# DorMouse-V0_5.net
KiCad netlist of a schematic drawn in EAGLE
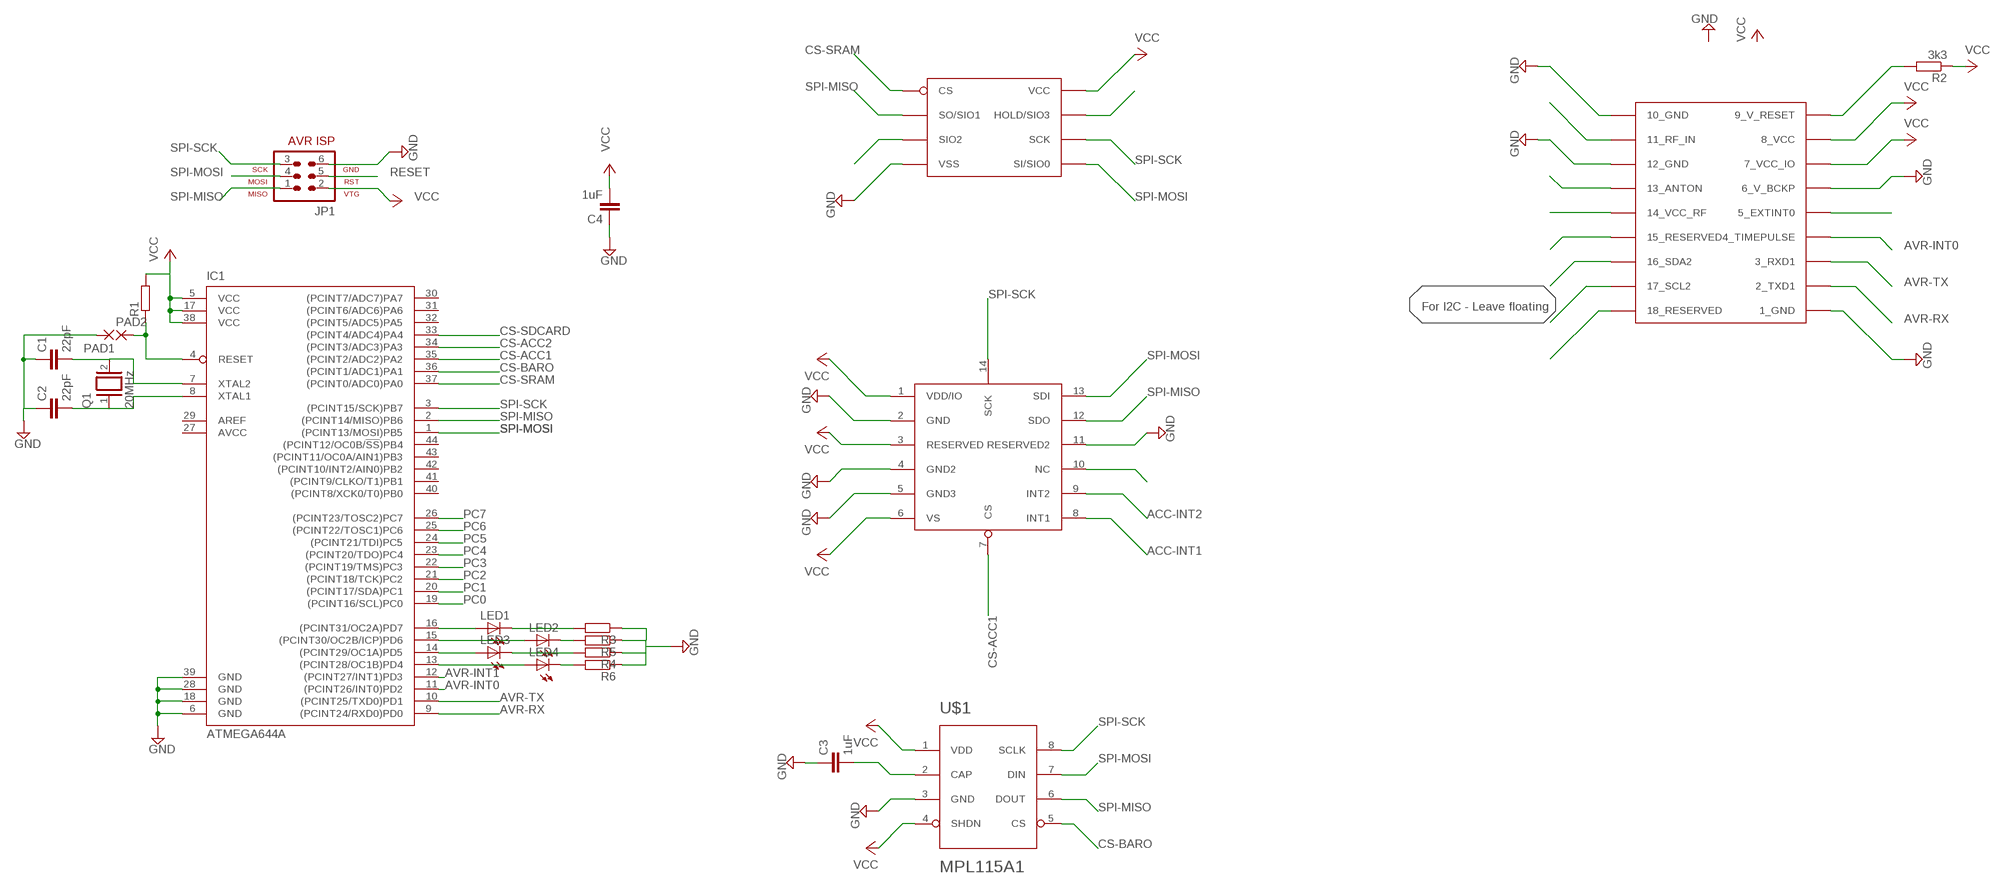
[diagram p0: schematic, sheet 1]

(export (version "E")
  (design (tool "Eeschema 10.0.6"))
  (components
    (comp (ref "C1")
      (value "22pF")
      (footprint "eagle-import:C0402")
      (libsource (lib "eagle-import") (part "C-EUC0402"))
    )
    (comp (ref "C2")
      (value "22pF")
      (footprint "eagle-import:C0402")
      (libsource (lib "eagle-import") (part "C-EUC0402"))
    )
    (comp (ref "C3")
      (value "1uF")
      (footprint "eagle-import:C0402")
      (libsource (lib "eagle-import") (part "C-EUC0402"))
    )
    (comp (ref "C4")
      (value "1uF")
      (footprint "eagle-import:C0402")
      (libsource (lib "eagle-import") (part "C-EUC0402"))
    )
    (comp (ref "IC1")
      (value "ATMEGA644A")
      (footprint "eagle-import:TQFP44")
      (fields (field (name "MPN") "ATMEGA644PV-10AU"))
      (libsource (lib "eagle-import") (part "ATMEGA644A"))
    )
    (comp (ref "JP1")
      (value "AVR-ISP-6")
      (footprint "eagle-import:AVR-ISP-6")
      (libsource (lib "eagle-import") (part "AVR-ISP-6"))
    )
    (comp (ref "LED1")
      (value "LEDCHIP-LED0603")
      (footprint "eagle-import:CHIP-LED0603")
      (libsource (lib "eagle-import") (part "LEDCHIP-LED0603"))
    )
    (comp (ref "LED2")
      (value "LEDCHIP-LED0603")
      (footprint "eagle-import:CHIP-LED0603")
      (libsource (lib "eagle-import") (part "LEDCHIP-LED0603"))
    )
    (comp (ref "LED3")
      (value "LEDCHIP-LED0603")
      (footprint "eagle-import:CHIP-LED0603")
      (libsource (lib "eagle-import") (part "LEDCHIP-LED0603"))
    )
    (comp (ref "LED4")
      (value "LEDCHIP-LED0603")
      (footprint "eagle-import:CHIP-LED0603")
      (libsource (lib "eagle-import") (part "LEDCHIP-LED0603"))
    )
    (comp (ref "PAD1")
      (value "SMD2")
      (footprint "eagle-import:SMD1,27-2,54")
      (libsource (lib "eagle-import") (part "SMD2"))
    )
    (comp (ref "PAD2")
      (value "SMD2")
      (footprint "eagle-import:SMD1,27-2,54")
      (libsource (lib "eagle-import") (part "SMD2"))
    )
    (comp (ref "Q1")
      (value "20MHz")
      (footprint "eagle-import:QS")
      (libsource (lib "eagle-import") (part "XTAL/S"))
    )
    (comp (ref "R1")
      (value "R-EU_R0402")
      (footprint "eagle-import:R0402")
      (libsource (lib "eagle-import") (part "R-EU_R0402"))
    )
    (comp (ref "R2")
      (value "3k3")
      (footprint "eagle-import:R0402")
      (libsource (lib "eagle-import") (part "R-EU_R0402"))
    )
    (comp (ref "R3")
      (value "R-EU_R0402")
      (footprint "eagle-import:R0402")
      (libsource (lib "eagle-import") (part "R-EU_R0402"))
    )
    (comp (ref "R4")
      (value "R-EU_R0402")
      (footprint "eagle-import:R0402")
      (libsource (lib "eagle-import") (part "R-EU_R0402"))
    )
    (comp (ref "R5")
      (value "R-EU_R0402")
      (footprint "eagle-import:R0402")
      (libsource (lib "eagle-import") (part "R-EU_R0402"))
    )
    (comp (ref "R6")
      (value "R-EU_R0402")
      (footprint "eagle-import:R0402")
      (libsource (lib "eagle-import") (part "R-EU_R0402"))
    )
    (comp (ref "SPI-SRAM")
      (value "23LC1024")
      (footprint "eagle-import:SOIC8")
      (libsource (lib "eagle-import") (part "23LC1024"))
    )
    (comp (ref "U$1")
      (value "MPL115A1")
      (footprint "eagle-import:LGA-8")
      (libsource (lib "eagle-import") (part "MPL115A1"))
    )
    (comp (ref "U$2")
      (value "ADXL345")
      (footprint "eagle-import:LGA-14")
      (libsource (lib "eagle-import") (part "ADXL345"))
    )
    (comp (ref "U$3")
      (value "UBLOX_MAX-6")
      (footprint "eagle-import:UBLOX_MAX-6")
      (libsource (lib "eagle-import") (part "UBLOX_MAX-6"))
    )
  )
  (nets
    (net (code "1") (name "/ACC-INT1") (class "Default")
      (node (ref "U$2") (pin "8") (pinfunction "INT1_8") (pintype "bidirectional"))
    )
    (net (code "2") (name "/ACC-INT2") (class "Default")
      (node (ref "U$2") (pin "9") (pinfunction "INT2_9") (pintype "bidirectional"))
    )
    (net (code "3") (name "/AVCC") (class "Default")
      (node (ref "IC1") (pin "27") (pinfunction "AVCC_27") (pintype "power_in"))
    )
    (net (code "4") (name "/AVR-INT0") (class "Default")
      (node (ref "IC1") (pin "11") (pinfunction "(PCINT26/INT0)PD2_11") (pintype "bidirectional"))
      (node (ref "U$3") (pin "4_TIMEPULSE") (pinfunction "4_TIMEPULSE_4_TIMEPULSE") (pintype "bidirectional"))
    )
    (net (code "5") (name "/AVR-INT1") (class "Default")
      (node (ref "IC1") (pin "12") (pinfunction "(PCINT27/INT1)PD3_12") (pintype "bidirectional"))
    )
    (net (code "6") (name "/AVR-RX") (class "Default")
      (node (ref "IC1") (pin "9") (pinfunction "(PCINT24/RXD0)PD0_9") (pintype "bidirectional"))
      (node (ref "U$3") (pin "2_TXD1") (pinfunction "2_TXD1_2_TXD1") (pintype "bidirectional"))
    )
    (net (code "7") (name "/AVR-TX") (class "Default")
      (node (ref "IC1") (pin "10") (pinfunction "(PCINT25/TXD0)PD1_10") (pintype "bidirectional"))
      (node (ref "U$3") (pin "3_RXD1") (pinfunction "3_RXD1_3_RXD1") (pintype "bidirectional"))
    )
    (net (code "8") (name "/CS-ACC1") (class "Default")
      (node (ref "IC1") (pin "35") (pinfunction "(PCINT2/ADC2)PA2_35") (pintype "bidirectional"))
      (node (ref "U$2") (pin "7") (pinfunction "CS_7") (pintype "bidirectional"))
    )
    (net (code "9") (name "/CS-ACC2") (class "Default")
      (node (ref "IC1") (pin "34") (pinfunction "(PCINT3/ADC3)PA3_34") (pintype "bidirectional"))
    )
    (net (code "10") (name "/CS-BARO") (class "Default")
      (node (ref "IC1") (pin "36") (pinfunction "(PCINT1/ADC1)PA1_36") (pintype "bidirectional"))
      (node (ref "U$1") (pin "5") (pinfunction "CS_5") (pintype "bidirectional"))
    )
    (net (code "11") (name "/CS-SDCARD") (class "Default")
      (node (ref "IC1") (pin "33") (pinfunction "(PCINT4/ADC4)PA4_33") (pintype "bidirectional"))
    )
    (net (code "12") (name "/CS-SRAM") (class "Default")
      (node (ref "IC1") (pin "37") (pinfunction "(PCINT0/ADC0)PA0_37") (pintype "bidirectional"))
      (node (ref "SPI-SRAM") (pin "1") (pinfunction "CS_1") (pintype "bidirectional"))
    )
    (net (code "13") (name "/PC0") (class "Default")
      (node (ref "IC1") (pin "19") (pinfunction "(PCINT16/SCL)PC0_19") (pintype "output"))
    )
    (net (code "14") (name "/PC1") (class "Default")
      (node (ref "IC1") (pin "20") (pinfunction "(PCINT17/SDA)PC1_20") (pintype "output"))
    )
    (net (code "15") (name "/PC2") (class "Default")
      (node (ref "IC1") (pin "21") (pinfunction "(PCINT18/TCK)PC2_21") (pintype "output"))
    )
    (net (code "16") (name "/PC3") (class "Default")
      (node (ref "IC1") (pin "22") (pinfunction "(PCINT19/TMS)PC3_22") (pintype "output"))
    )
    (net (code "17") (name "/PC4") (class "Default")
      (node (ref "IC1") (pin "23") (pinfunction "(PCINT20/TDO)PC4_23") (pintype "output"))
    )
    (net (code "18") (name "/PC5") (class "Default")
      (node (ref "IC1") (pin "24") (pinfunction "(PCINT21/TDI)PC5_24") (pintype "output"))
    )
    (net (code "19") (name "/PC6") (class "Default")
      (node (ref "IC1") (pin "25") (pinfunction "(PCINT22/TOSC1)PC6_25") (pintype "output"))
    )
    (net (code "20") (name "/PC7") (class "Default")
      (node (ref "IC1") (pin "26") (pinfunction "(PCINT23/TOSC2)PC7_26") (pintype "output"))
    )
    (net (code "21") (name "/RESET") (class "Default")
      (node (ref "IC1") (pin "4") (pinfunction "RESET_4") (pintype "input"))
      (node (ref "JP1") (pin "5") (pinfunction "5_5") (pintype "passive"))
      (node (ref "PAD2") (pin "1") (pinfunction "P_1") (pintype "passive"))
      (node (ref "R1") (pin "1") (pinfunction "1_1") (pintype "passive"))
    )
    (net (code "22") (name "/SPI-MISO") (class "Default")
      (node (ref "IC1") (pin "2") (pinfunction "(PCINT14/MISO)PB6_2") (pintype "bidirectional"))
      (node (ref "JP1") (pin "1") (pinfunction "1_1") (pintype "passive"))
      (node (ref "SPI-SRAM") (pin "2") (pinfunction "SO/SIO1_2") (pintype "bidirectional"))
      (node (ref "U$1") (pin "6") (pinfunction "DOUT_6") (pintype "bidirectional"))
      (node (ref "U$2") (pin "12") (pinfunction "SDO_12") (pintype "bidirectional"))
    )
    (net (code "23") (name "/SPI-MOSI") (class "Default")
      (node (ref "IC1") (pin "1") (pinfunction "(PCINT13/MOSI)PB5_1") (pintype "bidirectional"))
      (node (ref "JP1") (pin "4") (pinfunction "4_4") (pintype "passive"))
      (node (ref "SPI-SRAM") (pin "5") (pinfunction "SI/SIO0_5") (pintype "bidirectional"))
      (node (ref "U$1") (pin "7") (pinfunction "DIN_7") (pintype "bidirectional"))
      (node (ref "U$2") (pin "13") (pinfunction "SDI_13") (pintype "bidirectional"))
    )
    (net (code "24") (name "/SPI-SCK") (class "Default")
      (node (ref "IC1") (pin "3") (pinfunction "(PCINT15/SCK)PB7_3") (pintype "bidirectional"))
      (node (ref "JP1") (pin "3") (pinfunction "3_3") (pintype "passive"))
      (node (ref "SPI-SRAM") (pin "6") (pinfunction "SCK_6") (pintype "bidirectional"))
      (node (ref "U$1") (pin "8") (pinfunction "SCLK_8") (pintype "bidirectional"))
      (node (ref "U$2") (pin "14") (pinfunction "SCK_14") (pintype "bidirectional"))
    )
    (net (code "25") (name "GND") (class "Default")
      (node (ref "C1") (pin "1") (pinfunction "1_1") (pintype "passive"))
      (node (ref "C2") (pin "1") (pinfunction "1_1") (pintype "passive"))
      (node (ref "C3") (pin "1") (pinfunction "1_1") (pintype "passive"))
      (node (ref "C4") (pin "1") (pinfunction "1_1") (pintype "passive"))
      (node (ref "IC1") (pin "18") (pinfunction "GND_18") (pintype "power_in"))
      (node (ref "IC1") (pin "28") (pinfunction "GND_28") (pintype "power_in"))
      (node (ref "IC1") (pin "39") (pinfunction "GND_39") (pintype "power_in"))
      (node (ref "IC1") (pin "6") (pinfunction "GND_6") (pintype "power_in"))
      (node (ref "JP1") (pin "6") (pinfunction "6_6") (pintype "passive"))
      (node (ref "PAD1") (pin "1") (pinfunction "P_1") (pintype "passive"))
      (node (ref "R3") (pin "1") (pinfunction "1_1") (pintype "passive"))
      (node (ref "R4") (pin "1") (pinfunction "1_1") (pintype "passive"))
      (node (ref "R5") (pin "1") (pinfunction "1_1") (pintype "passive"))
      (node (ref "R6") (pin "1") (pinfunction "1_1") (pintype "passive"))
      (node (ref "SPI-SRAM") (pin "4") (pinfunction "VSS_4") (pintype "bidirectional"))
      (node (ref "U$1") (pin "3") (pinfunction "GND_3") (pintype "bidirectional"))
      (node (ref "U$2") (pin "11") (pinfunction "RESERVED2_11") (pintype "bidirectional"))
      (node (ref "U$2") (pin "2") (pinfunction "GND_2") (pintype "bidirectional"))
      (node (ref "U$2") (pin "4") (pinfunction "GND2_4") (pintype "bidirectional"))
      (node (ref "U$2") (pin "5") (pinfunction "GND3_5") (pintype "bidirectional"))
      (node (ref "U$3") (pin "10_GND") (pinfunction "10_GND_10_GND") (pintype "power_in"))
      (node (ref "U$3") (pin "12_GND") (pinfunction "12_GND_12_GND") (pintype "power_in"))
      (node (ref "U$3") (pin "1_GND") (pinfunction "1_GND_1_GND") (pintype "power_in"))
      (node (ref "U$3") (pin "6_V_BCKP") (pinfunction "6_V_BCKP_6_V_BCKP") (pintype "bidirectional"))
    )
    (net (code "26") (name "Net-(IC1-(PCINT28{slash}OC1B)PD4)") (class "Default")
      (node (ref "IC1") (pin "13") (pinfunction "(PCINT28/OC1B)PD4_13") (pintype "bidirectional"))
      (node (ref "LED4") (pin "A") (pinfunction "A_A") (pintype "passive"))
    )
    (net (code "27") (name "Net-(IC1-(PCINT29{slash}OC1A)PD5)") (class "Default")
      (node (ref "IC1") (pin "14") (pinfunction "(PCINT29/OC1A)PD5_14") (pintype "bidirectional"))
      (node (ref "LED3") (pin "A") (pinfunction "A_A") (pintype "passive"))
    )
    (net (code "28") (name "Net-(IC1-(PCINT30{slash}OC2B{slash}ICP)PD6)") (class "Default")
      (node (ref "IC1") (pin "15") (pinfunction "(PCINT30/OC2B/ICP)PD6_15") (pintype "bidirectional"))
      (node (ref "LED2") (pin "A") (pinfunction "A_A") (pintype "passive"))
    )
    (net (code "29") (name "Net-(IC1-(PCINT31{slash}OC2A)PD7)") (class "Default")
      (node (ref "IC1") (pin "16") (pinfunction "(PCINT31/OC2A)PD7_16") (pintype "bidirectional"))
      (node (ref "LED1") (pin "A") (pinfunction "A_A") (pintype "passive"))
    )
    (net (code "30") (name "Net-(IC1-XTAL1)") (class "Default")
      (node (ref "C2") (pin "2") (pinfunction "2_2") (pintype "passive"))
      (node (ref "IC1") (pin "8") (pinfunction "XTAL1_8") (pintype "bidirectional"))
      (node (ref "Q1") (pin "1") (pinfunction "1_1") (pintype "passive"))
    )
    (net (code "31") (name "Net-(IC1-XTAL2)") (class "Default")
      (node (ref "C1") (pin "2") (pinfunction "2_2") (pintype "passive"))
      (node (ref "IC1") (pin "7") (pinfunction "XTAL2_7") (pintype "bidirectional"))
      (node (ref "Q1") (pin "2") (pinfunction "2_2") (pintype "passive"))
    )
    (net (code "32") (name "Net-(LED1-PadC)") (class "Default")
      (node (ref "LED1") (pin "C") (pinfunction "C_C") (pintype "passive"))
      (node (ref "R3") (pin "2") (pinfunction "2_2") (pintype "passive"))
    )
    (net (code "33") (name "Net-(LED2-PadC)") (class "Default")
      (node (ref "LED2") (pin "C") (pinfunction "C_C") (pintype "passive"))
      (node (ref "R5") (pin "2") (pinfunction "2_2") (pintype "passive"))
    )
    (net (code "34") (name "Net-(LED3-PadC)") (class "Default")
      (node (ref "LED3") (pin "C") (pinfunction "C_C") (pintype "passive"))
      (node (ref "R4") (pin "2") (pinfunction "2_2") (pintype "passive"))
    )
    (net (code "35") (name "Net-(LED4-PadC)") (class "Default")
      (node (ref "LED4") (pin "C") (pinfunction "C_C") (pintype "passive"))
      (node (ref "R6") (pin "2") (pinfunction "2_2") (pintype "passive"))
    )
    (net (code "36") (name "Net-(R2-Pad2)") (class "Default")
      (node (ref "R2") (pin "2") (pinfunction "2_2") (pintype "passive"))
      (node (ref "U$3") (pin "9_V_RESET") (pinfunction "9_V_RESET_9_V_RESET") (pintype "power_in"))
    )
    (net (code "37") (name "Net-(U$1-CAP)") (class "Default")
      (node (ref "C3") (pin "2") (pinfunction "2_2") (pintype "passive"))
      (node (ref "U$1") (pin "2") (pinfunction "CAP_2") (pintype "bidirectional"))
    )
    (net (code "38") (name "VCC") (class "Default")
      (node (ref "C4") (pin "2") (pinfunction "2_2") (pintype "passive"))
      (node (ref "IC1") (pin "17") (pinfunction "VCC_17") (pintype "power_in"))
      (node (ref "IC1") (pin "38") (pinfunction "VCC_38") (pintype "power_in"))
      (node (ref "IC1") (pin "5") (pinfunction "VCC_5") (pintype "power_in"))
      (node (ref "JP1") (pin "2") (pinfunction "2_2") (pintype "passive"))
      (node (ref "R1") (pin "2") (pinfunction "2_2") (pintype "passive"))
      (node (ref "R2") (pin "1") (pinfunction "1_1") (pintype "passive"))
      (node (ref "SPI-SRAM") (pin "8") (pinfunction "VCC_8") (pintype "bidirectional"))
      (node (ref "U$1") (pin "1") (pinfunction "VDD_1") (pintype "bidirectional"))
      (node (ref "U$1") (pin "4") (pinfunction "SHDN_4") (pintype "bidirectional"))
      (node (ref "U$2") (pin "1") (pinfunction "VDD/IO_1") (pintype "bidirectional"))
      (node (ref "U$2") (pin "3") (pinfunction "RESERVED_3") (pintype "bidirectional"))
      (node (ref "U$2") (pin "6") (pinfunction "VS_6") (pintype "bidirectional"))
      (node (ref "U$3") (pin "7_VCC_IO") (pinfunction "7_VCC_IO_7_VCC_IO") (pintype "power_in"))
      (node (ref "U$3") (pin "8_VCC") (pinfunction "8_VCC_8_VCC") (pintype "power_in"))
    )
    (net (code "39") (name "unconnected-(IC1-(PCINT5{slash}ADC5)PA5-Pad32)") (class "Default")
      (node (ref "IC1") (pin "32") (pinfunction "(PCINT5/ADC5)PA5_32") (pintype "bidirectional"))
    )
    (net (code "40") (name "unconnected-(IC1-(PCINT6{slash}ADC6)PA6-Pad31)") (class "Default")
      (node (ref "IC1") (pin "31") (pinfunction "(PCINT6/ADC6)PA6_31") (pintype "bidirectional"))
    )
    (net (code "41") (name "unconnected-(IC1-(PCINT7{slash}ADC7)PA7-Pad30)") (class "Default")
      (node (ref "IC1") (pin "30") (pinfunction "(PCINT7/ADC7)PA7_30") (pintype "bidirectional"))
    )
    (net (code "42") (name "unconnected-(IC1-(PCINT8{slash}XCK0{slash}T0)PB0-Pad40)") (class "Default")
      (node (ref "IC1") (pin "40") (pinfunction "(PCINT8/XCK0/T0)PB0_40") (pintype "bidirectional"))
    )
    (net (code "43") (name "unconnected-(IC1-(PCINT9{slash}CLKO{slash}T1)PB1-Pad41)") (class "Default")
      (node (ref "IC1") (pin "41") (pinfunction "(PCINT9/CLKO/T1)PB1_41") (pintype "bidirectional"))
    )
    (net (code "44") (name "unconnected-(IC1-(PCINT10{slash}INT2{slash}AIN0)PB2-Pad42)") (class "Default")
      (node (ref "IC1") (pin "42") (pinfunction "(PCINT10/INT2/AIN0)PB2_42") (pintype "bidirectional"))
    )
    (net (code "45") (name "unconnected-(IC1-(PCINT11{slash}OC0A{slash}AIN1)PB3-Pad43)") (class "Default")
      (node (ref "IC1") (pin "43") (pinfunction "(PCINT11/OC0A/AIN1)PB3_43") (pintype "bidirectional"))
    )
    (net (code "46") (name "unconnected-(IC1-(PCINT12{slash}OC0B{slash}~{SS})PB4-Pad44)") (class "Default")
      (node (ref "IC1") (pin "44") (pinfunction "(PCINT12/OC0B/~{SS})PB4_44") (pintype "bidirectional"))
    )
    (net (code "47") (name "unconnected-(IC1-AREF-Pad29)") (class "Default")
      (node (ref "IC1") (pin "29") (pinfunction "AREF_29") (pintype "passive"))
    )
    (net (code "48") (name "unconnected-(SPI-SRAM-HOLD{slash}SIO3-Pad7)") (class "Default")
      (node (ref "SPI-SRAM") (pin "7") (pinfunction "HOLD/SIO3_7") (pintype "bidirectional"))
    )
    (net (code "49") (name "unconnected-(SPI-SRAM-SIO2-Pad3)") (class "Default")
      (node (ref "SPI-SRAM") (pin "3") (pinfunction "SIO2_3") (pintype "bidirectional"))
    )
    (net (code "50") (name "unconnected-(U$2-NC-Pad10)") (class "Default")
      (node (ref "U$2") (pin "10") (pinfunction "NC_10") (pintype "bidirectional"))
    )
    (net (code "51") (name "unconnected-(U$3-Pad5_EXTINT0)") (class "Default")
      (node (ref "U$3") (pin "5_EXTINT0") (pinfunction "5_EXTINT0_5_EXTINT0") (pintype "bidirectional"))
    )
    (net (code "52") (name "unconnected-(U$3-Pad11_RF_IN)") (class "Default")
      (node (ref "U$3") (pin "11_RF_IN") (pinfunction "11_RF_IN_11_RF_IN") (pintype "bidirectional"))
    )
    (net (code "53") (name "unconnected-(U$3-Pad13_ANTON)") (class "Default")
      (node (ref "U$3") (pin "13_ANTON") (pinfunction "13_ANTON_13_ANTON") (pintype "bidirectional"))
    )
    (net (code "54") (name "unconnected-(U$3-Pad14_VCC_RF)") (class "Default")
      (node (ref "U$3") (pin "14_VCC_RF") (pinfunction "14_VCC_RF_14_VCC_RF") (pintype "bidirectional"))
    )
    (net (code "55") (name "unconnected-(U$3-Pad15_RESERVED)") (class "Default")
      (node (ref "U$3") (pin "15_RESERVED") (pinfunction "15_RESERVED_15_RESERVED") (pintype "bidirectional"))
    )
    (net (code "56") (name "unconnected-(U$3-Pad16_SDA2)") (class "Default")
      (node (ref "U$3") (pin "16_SDA2") (pinfunction "16_SDA2_16_SDA2") (pintype "bidirectional"))
    )
    (net (code "57") (name "unconnected-(U$3-Pad17_SCL2)") (class "Default")
      (node (ref "U$3") (pin "17_SCL2") (pinfunction "17_SCL2_17_SCL2") (pintype "bidirectional"))
    )
    (net (code "58") (name "unconnected-(U$3-Pad18_RESERVED)") (class "Default")
      (node (ref "U$3") (pin "18_RESERVED") (pinfunction "18_RESERVED_18_RESERVED") (pintype "bidirectional"))
    )
  )
)
